# 2021-01-21_HALO_RGB_Board-Autorouted.net
KiCad netlist of a schematic drawn in EAGLE
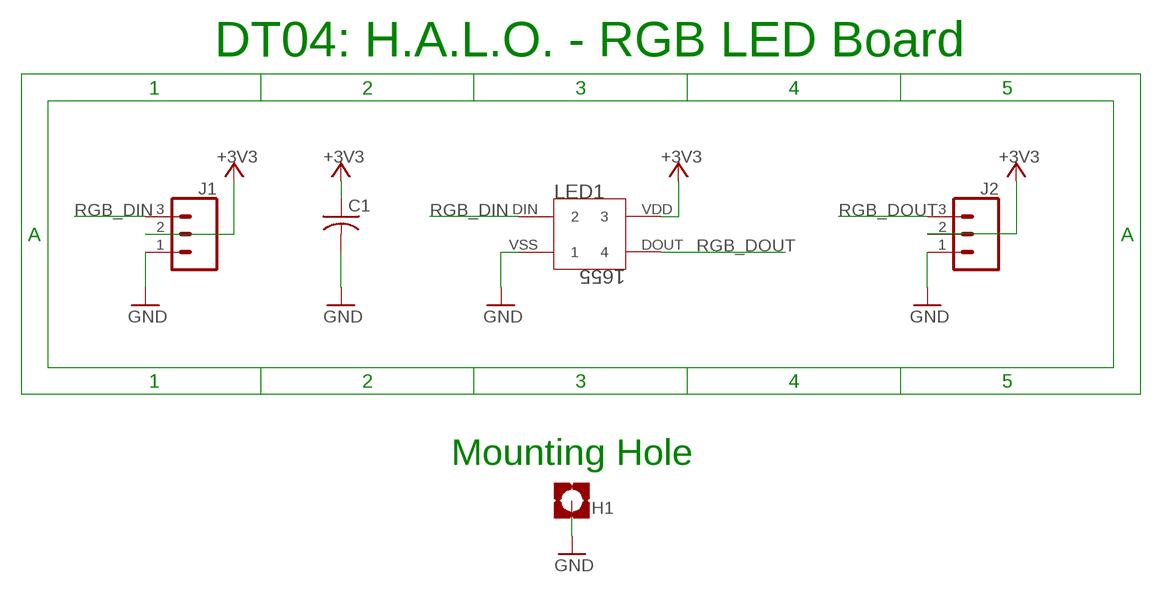
[diagram p0: schematic, sheet 1]

(export (version "E")
  (design (tool "Eeschema 10.0.6"))
  (components
    (comp (ref "C1")
      (value "1uF")
      (footprint "eagle-import:C0805")
      (libsource (lib "eagle-import") (part "C-USC0805"))
    )
    (comp (ref "H1")
      (value "MOUNT-PAD-SQUARE3.0")
      (footprint "eagle-import:3,0-PAD-SQUARE")
      (libsource (lib "eagle-import") (part "MOUNT-PAD-SQUARE3.0"))
    )
    (comp (ref "J1")
      (value "CONN_03LOCK")
      (footprint "eagle-import:1X03_LOCK")
      (libsource (lib "eagle-import") (part "CONN_03LOCK"))
    )
    (comp (ref "J2")
      (value "CONN_03LOCK")
      (footprint "eagle-import:1X03_LOCK")
      (libsource (lib "eagle-import") (part "CONN_03LOCK"))
    )
    (comp (ref "LED1")
      (value "1655")
      (footprint "eagle-import:LED_1655_ADA")
      (fields (field (name "COPYRIGHT") "Copyright (C) 2018 Accelerated Designs. All rights reserved"))
      (libsource (lib "eagle-import") (part "1655"))
    )
  )
  (nets
    (net (code "1") (name "+3V3") (class "Default")
      (node (ref "C1") (pin "1") (pinfunction "1_1") (pintype "passive"))
      (node (ref "J1") (pin "2") (pinfunction "2_2") (pintype "passive"))
      (node (ref "J2") (pin "2") (pinfunction "2_2") (pintype "passive"))
      (node (ref "LED1") (pin "VDD") (pinfunction "3_VDD") (pintype "passive"))
    )
    (net (code "2") (name "/RGB_DIN") (class "Default")
      (node (ref "J1") (pin "3") (pinfunction "3_3") (pintype "passive"))
      (node (ref "LED1") (pin "DIN") (pinfunction "2_DIN") (pintype "passive"))
    )
    (net (code "3") (name "/RGB_DOUT") (class "Default")
      (node (ref "J2") (pin "3") (pinfunction "3_3") (pintype "passive"))
      (node (ref "LED1") (pin "DOUT") (pinfunction "4_DOUT") (pintype "passive"))
    )
    (net (code "4") (name "GND") (class "Default")
      (node (ref "C1") (pin "2") (pinfunction "2_2") (pintype "passive"))
      (node (ref "H1") (pin "B3,0") (pinfunction "MOUNT_B3,0") (pintype "passive"))
      (node (ref "J1") (pin "1") (pinfunction "1_1") (pintype "passive"))
      (node (ref "J2") (pin "1") (pinfunction "1_1") (pintype "passive"))
      (node (ref "LED1") (pin "VSS") (pinfunction "1_VSS") (pintype "passive"))
    )
  )
)
